# Medusa_9x8.net
KiCad netlist of a schematic drawn in Altium Designer
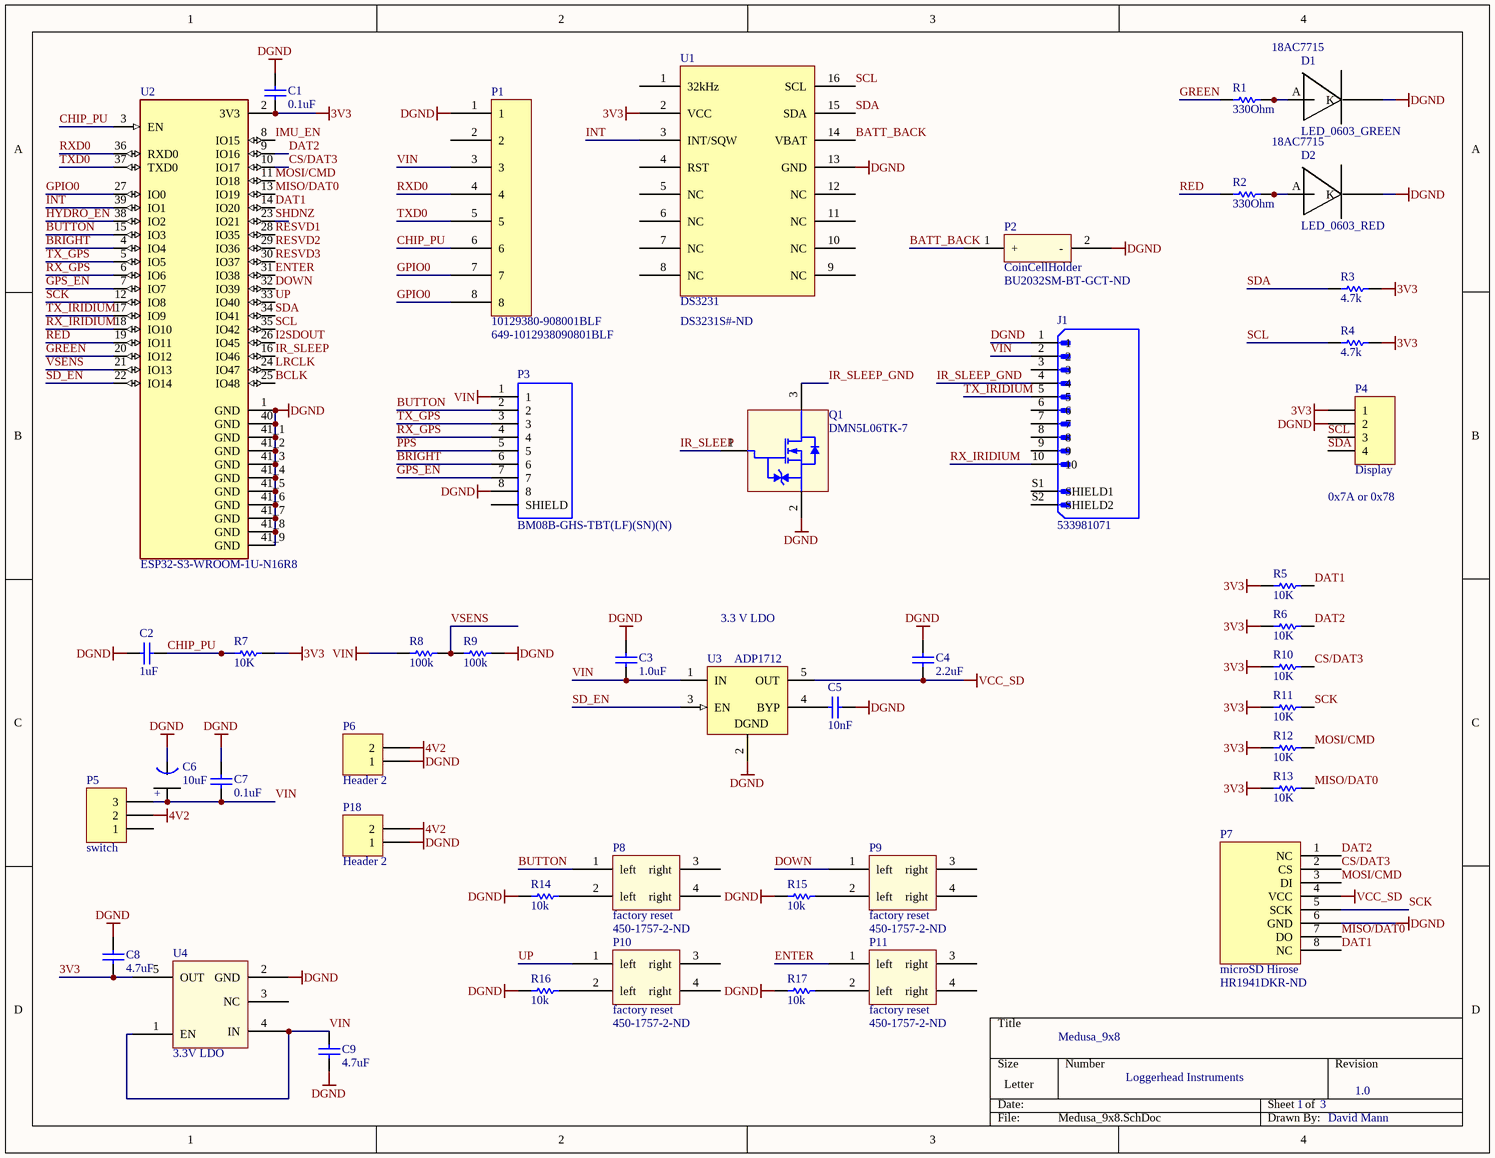
[diagram p0: Medusa_9x8.SchDoc]

(export (version "E")
  (design (tool "Eeschema 10.0.6"))
  (components
    (comp (ref "C1")
      (value "0.1uF")
      (footprint "0402")
      (description "Ceramic Chip Capacitor - Standard")
      (fields (field (name "PUBLISHER") "Altium Limited"))
      (libsource (lib "KEMET Chip Capacitor") (part "C0402"))
    )
    (comp (ref "C2")
      (value "1uF")
      (footprint "0402")
      (description "Ceramic Chip Capacitor - Standard")
      (fields (field (name "PUBLISHER") "Altium Limited"))
      (libsource (lib "KEMET Chip Capacitor") (part "C0402"))
    )
    (comp (ref "C3")
      (value "1.0uF")
      (footprint "0402")
      (description "Ceramic Chip Capacitor - Standard")
      (fields (field (name "PUBLISHER") "Altium Limited"))
      (libsource (lib "KEMET Chip Capacitor") (part "C0402"))
    )
    (comp (ref "C4")
      (value "2.2uF")
      (footprint "0402")
      (description "Ceramic Chip Capacitor - Standard")
      (fields (field (name "PUBLISHER") "Altium Limited"))
      (libsource (lib "KEMET Chip Capacitor") (part "C0402"))
    )
    (comp (ref "C5")
      (value "10nF")
      (footprint "0402")
      (description "Ceramic Chip Capacitor - Standard")
      (fields (field (name "PUBLISHER") "Altium Limited"))
      (libsource (lib "KEMET Chip Capacitor") (part "C0402"))
    )
    (comp (ref "C6") (value "10uF") (footprint "Tant0805") (libsource (lib "Loggerhead") (part "Tant0805")))
    (comp (ref "C7")
      (value "0.1uF")
      (footprint "0402")
      (description "Ceramic Chip Capacitor - Standard")
      (fields (field (name "PUBLISHER") "Altium Limited"))
      (libsource (lib "KEMET Chip Capacitor") (part "C0402"))
    )
    (comp (ref "C8")
      (value "4.7uF")
      (footprint "0402")
      (description "Ceramic Chip Capacitor - Standard")
      (fields (field (name "PUBLISHER") "Altium Limited"))
      (libsource (lib "KEMET Chip Capacitor") (part "C0402"))
    )
    (comp (ref "C9")
      (value "4.7uF")
      (footprint "0402")
      (description "Ceramic Chip Capacitor - Standard")
      (fields (field (name "PUBLISHER") "Altium Limited"))
      (libsource (lib "KEMET Chip Capacitor") (part "C0402"))
    )
    (comp (ref "D1")
      (value "LED_0603_GREEN")
      (footprint "Diode0603")
      (fields (field (name "SUPPLIER PART NUMBER 1") "18AC7715"))
      (libsource (lib "Loggerhead") (part "LED_0603"))
    )
    (comp (ref "D2")
      (value "LED_0603_RED")
      (footprint "Diode0603")
      (fields (field (name "SUPPLIER PART NUMBER 1") "18AC7715"))
      (libsource (lib "Loggerhead") (part "LED_0603"))
    )
    (comp (ref "J1")
      (value "533981071")
      (footprint "MOLEX_533981071")
      (libsource (lib "533981071") (part "533981071"))
    )
    (comp (ref "P1")
      (value "10129380-908001BLF")
      (footprint "Header_8_SMT")
      (description "Surface mount header")
      (fields (field (name "SUPPLIER PART NUMBER 1") "649-1012938090801BLF"))
      (libsource (lib "Loggerhead") (part "Header8_SMT"))
    )
    (comp (ref "P2")
      (value "CoinCellHolder")
      (footprint "CoinCellHolder")
      (fields (field (name "SUPPLIER PART NUMBER 1") "BU2032SM-BT-GCT-ND"))
      (libsource (lib "Loggerhead") (part "CoinCellHolder"))
    )
    (comp (ref "P3")
      (value "BM08B-GHS-TBT(LF)(SN)(N)")
      (footprint "JST_BM08B-GHS-TBT(LF)(SN)(N)")
      (description "Connector Header Surface Mount 8 position 0.049 _1.25mm_")
      (fields (field (name "MF") "JST Sales") (field (name "MP") "BM08B-GHS-TBT_LF__SN__N_"))
      (libsource (lib "BM08B-GHS-TBT_LF__SN__N_") (part "BM08B-GHS-TBT(LF)(SN)(N)"))
    )
    (comp (ref "P4")
      (value "Display")
      (footprint "HDR1X4")
      (description "Header, 4-Pin")
      (fields (field (name "PUBLISHER") "Altium Limited"))
      (libsource (lib "Miscellaneous Connectors") (part "Header 4"))
    )
    (comp (ref "P5")
      (value "switch")
      (footprint "HDR1X3")
      (description "Header, 3-Pin")
      (fields (field (name "PUBLISHER") "Altium Limited"))
      (libsource (lib "Miscellaneous Connectors") (part "Header 3"))
    )
    (comp (ref "P6")
      (value "Header 2")
      (footprint "HDR1X2")
      (description "Header, 2-Pin")
      (fields (field (name "PUBLISHER") "Altium Limited"))
      (libsource (lib "Miscellaneous Connectors") (part "Header 2"))
    )
    (comp (ref "P7")
      (value "microSD Hirose")
      (footprint "DM3D microSD")
      (fields (field (name "SUPPLIER PART NUMBER 1") "HR1941DKR-ND"))
      (libsource (lib "Loggerhead") (part "microSD Hirose"))
    )
    (comp (ref "P8")
      (value "factory reset")
      (footprint "SOP4")
      (fields (field (name "SUPPLIER PART NUMBER 1") "450-1757-2-ND"))
      (libsource (lib "Loggerhead") (part "pushbutton"))
    )
    (comp (ref "P9")
      (value "factory reset")
      (footprint "SOP4")
      (fields (field (name "SUPPLIER PART NUMBER 1") "450-1757-2-ND"))
      (libsource (lib "Loggerhead") (part "pushbutton"))
    )
    (comp (ref "P10")
      (value "factory reset")
      (footprint "SOP4")
      (fields (field (name "SUPPLIER PART NUMBER 1") "450-1757-2-ND"))
      (libsource (lib "Loggerhead") (part "pushbutton"))
    )
    (comp (ref "P11")
      (value "factory reset")
      (footprint "SOP4")
      (fields (field (name "SUPPLIER PART NUMBER 1") "450-1757-2-ND"))
      (libsource (lib "Loggerhead") (part "pushbutton"))
    )
    (comp (ref "P18")
      (value "Header 2")
      (footprint "HDR1X2")
      (description "Header, 2-Pin")
      (fields (field (name "PUBLISHER") "Altium Limited"))
      (libsource (lib "Miscellaneous Connectors") (part "Header 2"))
    )
    (comp (ref "Q1")
      (value "DMN5L06TK-7")
      (footprint "SOT-523")
      (description "Ultra-low leakage Enhanced MOSFET")
      (fields
        (field (name "CREATOR AND DATE") "Will Flanery 2010-09-02")
        (field (name "FOOTPRINT VERIFIED BY") "*")
        (field (name "SCHEMATIC VERIFIED BY") "*")
        (field (name "VENDOR INFO VERIFIED BY") "*")
      )
      (libsource (lib "Flanery") (part "FET DMN5L06TK-7"))
    )
    (comp (ref "R1")
      (value "330Ohm")
      (footprint "2-0402")
      (fields (field (name "PUBLISHER") "Altium Limited"))
      (libsource (lib "Panasonic Resistor") (part "ERJ2RB"))
    )
    (comp (ref "R2")
      (value "330Ohm")
      (footprint "2-0402")
      (fields (field (name "PUBLISHER") "Altium Limited"))
      (libsource (lib "Panasonic Resistor") (part "ERJ2RB"))
    )
    (comp (ref "R3")
      (value "4.7k")
      (footprint "2-0402")
      (fields (field (name "PUBLISHER") "Altium Limited"))
      (libsource (lib "Panasonic Resistor") (part "ERJ2RB"))
    )
    (comp (ref "R4")
      (value "4.7k")
      (footprint "2-0402")
      (fields (field (name "PUBLISHER") "Altium Limited"))
      (libsource (lib "Panasonic Resistor") (part "ERJ2RB"))
    )
    (comp (ref "R5")
      (value "10K")
      (footprint "2-0402")
      (fields (field (name "PUBLISHER") "Altium Limited"))
      (libsource (lib "Panasonic Resistor") (part "ERJ2RB"))
    )
    (comp (ref "R6")
      (value "10K")
      (footprint "2-0402")
      (fields (field (name "PUBLISHER") "Altium Limited"))
      (libsource (lib "Panasonic Resistor") (part "ERJ2RB"))
    )
    (comp (ref "R7")
      (value "10K")
      (footprint "2-0402")
      (fields (field (name "PUBLISHER") "Altium Limited"))
      (libsource (lib "Panasonic Resistor") (part "ERJ2RB"))
    )
    (comp (ref "R8")
      (value "100k")
      (footprint "2-0402")
      (fields (field (name "PUBLISHER") "Altium Limited"))
      (libsource (lib "Panasonic Resistor") (part "ERJ2RB"))
    )
    (comp (ref "R9")
      (value "100k")
      (footprint "2-0402")
      (fields (field (name "PUBLISHER") "Altium Limited"))
      (libsource (lib "Panasonic Resistor") (part "ERJ2RB"))
    )
    (comp (ref "R10")
      (value "10K")
      (footprint "2-0402")
      (fields (field (name "PUBLISHER") "Altium Limited"))
      (libsource (lib "Panasonic Resistor") (part "ERJ2RB"))
    )
    (comp (ref "R11")
      (value "10K")
      (footprint "2-0402")
      (fields (field (name "PUBLISHER") "Altium Limited"))
      (libsource (lib "Panasonic Resistor") (part "ERJ2RB"))
    )
    (comp (ref "R12")
      (value "10K")
      (footprint "2-0402")
      (fields (field (name "PUBLISHER") "Altium Limited"))
      (libsource (lib "Panasonic Resistor") (part "ERJ2RB"))
    )
    (comp (ref "R13")
      (value "10K")
      (footprint "2-0402")
      (fields (field (name "PUBLISHER") "Altium Limited"))
      (libsource (lib "Panasonic Resistor") (part "ERJ2RB"))
    )
    (comp (ref "R14")
      (value "10k")
      (footprint "2-0402")
      (fields (field (name "PUBLISHER") "Altium Limited"))
      (libsource (lib "Panasonic Resistor") (part "ERJ2RB"))
    )
    (comp (ref "R15")
      (value "10k")
      (footprint "2-0402")
      (fields (field (name "PUBLISHER") "Altium Limited"))
      (libsource (lib "Panasonic Resistor") (part "ERJ2RB"))
    )
    (comp (ref "R16")
      (value "10k")
      (footprint "2-0402")
      (fields (field (name "PUBLISHER") "Altium Limited"))
      (libsource (lib "Panasonic Resistor") (part "ERJ2RB"))
    )
    (comp (ref "R17")
      (value "10k")
      (footprint "2-0402")
      (fields (field (name "PUBLISHER") "Altium Limited"))
      (libsource (lib "Panasonic Resistor") (part "ERJ2RB"))
    )
    (comp (ref "U1")
      (value "DS3231")
      (footprint "DS3231")
      (fields (field (name "SUPPLIER PART NUMBER 1") "DS3231S#-ND"))
      (libsource (lib "Loggerhead") (part "DS3231"))
    )
    (comp (ref "U2")
      (value "ESP32-S3-WROOM-1U-N16R8")
      (footprint "XCVR_ESP32-S3-WROOM-1U-N16R8")
      (fields (field (name "MF") "Espressif Systems"))
      (libsource (lib "ESP32-S3-WROOM-1U-N16R8") (part "ESP32-S3-WROOM-1U-N16R8"))
    )
    (comp (ref "U3")
      (value "ADP1712")
      (footprint "MF05A_N")
      (description "Micropower, 150mA Low-Noise Ultra Low-Dropout CMOS Voltage Regulator")
      (fields
        (field (name "PARTNUMBER") "LP3985IM5-3.3")
        (field (name "MANUFACTURER") "National Semiconductor")
        (field (name "PUBLISHER") "Altium Limited")
      )
      (libsource (lib "NSC LDO") (part "LP3985IM5-3.3"))
    )
    (comp (ref "U4")
      (value "3.3V LDO")
      (footprint "AP7361C-33Y5-13")
      (libsource (lib "Loggerhead") (part "AP7361C-33Y5-13"))
    )
  )
  (nets
    (net (code "1") (name "/BATT_BACK") (class "Default")
      (node (ref "P2") (pin "1") (pinfunction "+_1") (pintype "passive"))
      (node (ref "U1") (pin "14") (pinfunction "VBAT_14") (pintype "power_in"))
    )
    (net (code "2") (name "/BCLK") (class "Default")
      (node (ref "U2") (pin "25") (pinfunction "IO48_25") (pintype "bidirectional"))
    )
    (net (code "3") (name "/BRIGHT") (class "Default")
      (node (ref "P3") (pin "6") (pinfunction "6_6") (pintype "passive"))
      (node (ref "U2") (pin "4") (pinfunction "IO4_4") (pintype "bidirectional"))
    )
    (net (code "4") (name "/BUTTON") (class "Default")
      (node (ref "P3") (pin "2") (pinfunction "2_2") (pintype "passive"))
      (node (ref "P8") (pin "1") (pinfunction "left_1") (pintype "passive"))
      (node (ref "U2") (pin "15") (pinfunction "IO3_15") (pintype "bidirectional"))
    )
    (net (code "5") (name "/CHIP_PU") (class "Default")
      (node (ref "C2") (pin "1") (pinfunction "1_1") (pintype "passive"))
      (node (ref "P1") (pin "6") (pinfunction "6_6") (pintype "passive"))
      (node (ref "R7") (pin "2") (pinfunction "2_2") (pintype "passive"))
      (node (ref "U2") (pin "3") (pinfunction "EN_3") (pintype "input"))
    )
    (net (code "6") (name "/CS{slash}DAT3") (class "Default")
      (node (ref "P7") (pin "2") (pinfunction "CS_2") (pintype "passive"))
      (node (ref "R10") (pin "1") (pinfunction "1_1") (pintype "passive"))
      (node (ref "U2") (pin "10") (pinfunction "IO17_10") (pintype "bidirectional"))
    )
    (net (code "7") (name "/DAT1") (class "Default")
      (node (ref "P7") (pin "8") (pinfunction "NC_8") (pintype "passive"))
      (node (ref "R5") (pin "1") (pinfunction "1_1") (pintype "passive"))
      (node (ref "U2") (pin "14") (pinfunction "IO20_14") (pintype "bidirectional"))
    )
    (net (code "8") (name "/DAT2") (class "Default")
      (node (ref "P7") (pin "1") (pinfunction "NC_1") (pintype "passive"))
      (node (ref "R6") (pin "1") (pinfunction "1_1") (pintype "passive"))
      (node (ref "U2") (pin "9") (pinfunction "IO16_9") (pintype "bidirectional"))
    )
    (net (code "9") (name "/DOWN") (class "Default")
      (node (ref "P9") (pin "1") (pinfunction "left_1") (pintype "passive"))
      (node (ref "U2") (pin "32") (pinfunction "IO39_32") (pintype "bidirectional"))
    )
    (net (code "10") (name "/ENTER") (class "Default")
      (node (ref "P11") (pin "1") (pinfunction "left_1") (pintype "passive"))
      (node (ref "U2") (pin "31") (pinfunction "IO38_31") (pintype "bidirectional"))
    )
    (net (code "11") (name "/GPIO0") (class "Default")
      (node (ref "P1") (pin "7") (pinfunction "7_7") (pintype "passive"))
      (node (ref "P1") (pin "8") (pinfunction "8_8") (pintype "passive"))
      (node (ref "U2") (pin "27") (pinfunction "IO0_27") (pintype "bidirectional"))
    )
    (net (code "12") (name "/GPS_EN") (class "Default")
      (node (ref "P3") (pin "7") (pinfunction "7_7") (pintype "passive"))
      (node (ref "U2") (pin "7") (pinfunction "IO7_7") (pintype "bidirectional"))
    )
    (net (code "13") (name "/GREEN") (class "Default")
      (node (ref "R1") (pin "2") (pinfunction "2_2") (pintype "passive"))
      (node (ref "U2") (pin "20") (pinfunction "IO12_20") (pintype "bidirectional"))
    )
    (net (code "14") (name "/HYDRO_EN") (class "Default")
      (node (ref "U2") (pin "38") (pinfunction "IO2_38") (pintype "bidirectional"))
    )
    (net (code "15") (name "/I2SDOUT") (class "Default")
      (node (ref "U2") (pin "26") (pinfunction "IO45_26") (pintype "bidirectional"))
    )
    (net (code "16") (name "/IMU_EN") (class "Default")
      (node (ref "U2") (pin "8") (pinfunction "IO15_8") (pintype "bidirectional"))
    )
    (net (code "17") (name "/INT") (class "Default")
      (node (ref "U1") (pin "3") (pinfunction "INT/SQW_3") (pintype "passive"))
      (node (ref "U2") (pin "39") (pinfunction "IO1_39") (pintype "bidirectional"))
    )
    (net (code "18") (name "/IR_SLEEP") (class "Default")
      (node (ref "Q1") (pin "1") (pinfunction "G_1") (pintype "passive"))
      (node (ref "U2") (pin "16") (pinfunction "IO46_16") (pintype "bidirectional"))
    )
    (net (code "19") (name "/IR_SLEEP_GND") (class "Default")
      (node (ref "J1") (pin "4") (pinfunction "4_4") (pintype "passive"))
      (node (ref "Q1") (pin "3") (pinfunction "D_3") (pintype "passive"))
    )
    (net (code "20") (name "/LRCLK") (class "Default")
      (node (ref "U2") (pin "24") (pinfunction "IO47_24") (pintype "bidirectional"))
    )
    (net (code "21") (name "/MISO{slash}DAT0") (class "Default")
      (node (ref "P7") (pin "7") (pinfunction "DO_7") (pintype "passive"))
      (node (ref "R13") (pin "1") (pinfunction "1_1") (pintype "passive"))
      (node (ref "U2") (pin "13") (pinfunction "IO19_13") (pintype "bidirectional"))
    )
    (net (code "22") (name "/MOSI{slash}CMD") (class "Default")
      (node (ref "P7") (pin "3") (pinfunction "DI_3") (pintype "passive"))
      (node (ref "R12") (pin "1") (pinfunction "1_1") (pintype "passive"))
      (node (ref "U2") (pin "11") (pinfunction "IO18_11") (pintype "bidirectional"))
    )
    (net (code "23") (name "/PPS") (class "Default")
      (node (ref "P3") (pin "5") (pinfunction "5_5") (pintype "passive"))
    )
    (net (code "24") (name "/RED") (class "Default")
      (node (ref "R2") (pin "2") (pinfunction "2_2") (pintype "passive"))
      (node (ref "U2") (pin "19") (pinfunction "IO11_19") (pintype "bidirectional"))
    )
    (net (code "25") (name "/RESVD1") (class "Default")
      (node (ref "U2") (pin "28") (pinfunction "IO35_28") (pintype "bidirectional"))
    )
    (net (code "26") (name "/RESVD2") (class "Default")
      (node (ref "U2") (pin "29") (pinfunction "IO36_29") (pintype "bidirectional"))
    )
    (net (code "27") (name "/RESVD3") (class "Default")
      (node (ref "U2") (pin "30") (pinfunction "IO37_30") (pintype "bidirectional"))
    )
    (net (code "28") (name "/RXD0") (class "Default")
      (node (ref "P1") (pin "4") (pinfunction "4_4") (pintype "passive"))
      (node (ref "U2") (pin "36") (pinfunction "RXD0_36") (pintype "bidirectional"))
    )
    (net (code "29") (name "/RX_GPS") (class "Default")
      (node (ref "P3") (pin "4") (pinfunction "4_4") (pintype "passive"))
      (node (ref "U2") (pin "6") (pinfunction "IO6_6") (pintype "bidirectional"))
    )
    (net (code "30") (name "/RX_IRIDIUM") (class "Default")
      (node (ref "J1") (pin "10") (pinfunction "10_10") (pintype "passive"))
      (node (ref "U2") (pin "18") (pinfunction "IO10_18") (pintype "bidirectional"))
    )
    (net (code "31") (name "/SCK") (class "Default")
      (node (ref "P7") (pin "5") (pinfunction "SCK_5") (pintype "passive"))
      (node (ref "R11") (pin "1") (pinfunction "1_1") (pintype "passive"))
      (node (ref "U2") (pin "12") (pinfunction "IO8_12") (pintype "bidirectional"))
    )
    (net (code "32") (name "/SCL") (class "Default")
      (node (ref "P4") (pin "3") (pinfunction "3_3") (pintype "passive"))
      (node (ref "R4") (pin "2") (pinfunction "2_2") (pintype "passive"))
      (node (ref "U1") (pin "16") (pinfunction "SCL_16") (pintype "passive"))
      (node (ref "U2") (pin "35") (pinfunction "IO42_35") (pintype "bidirectional"))
    )
    (net (code "33") (name "/SDA") (class "Default")
      (node (ref "P4") (pin "4") (pinfunction "4_4") (pintype "passive"))
      (node (ref "R3") (pin "2") (pinfunction "2_2") (pintype "passive"))
      (node (ref "U1") (pin "15") (pinfunction "SDA_15") (pintype "passive"))
      (node (ref "U2") (pin "34") (pinfunction "IO41_34") (pintype "bidirectional"))
    )
    (net (code "34") (name "/SD_EN") (class "Default")
      (node (ref "U2") (pin "22") (pinfunction "IO14_22") (pintype "bidirectional"))
      (node (ref "U3") (pin "3") (pinfunction "EN_3") (pintype "input"))
    )
    (net (code "35") (name "/SHDNZ") (class "Default")
      (node (ref "U2") (pin "23") (pinfunction "IO21_23") (pintype "bidirectional"))
    )
    (net (code "36") (name "/TXD0") (class "Default")
      (node (ref "P1") (pin "5") (pinfunction "5_5") (pintype "passive"))
      (node (ref "U2") (pin "37") (pinfunction "TXD0_37") (pintype "bidirectional"))
    )
    (net (code "37") (name "/TX_GPS") (class "Default")
      (node (ref "P3") (pin "3") (pinfunction "3_3") (pintype "passive"))
      (node (ref "U2") (pin "5") (pinfunction "IO5_5") (pintype "bidirectional"))
    )
    (net (code "38") (name "/TX_IRIDIUM") (class "Default")
      (node (ref "J1") (pin "5") (pinfunction "5_5") (pintype "passive"))
      (node (ref "U2") (pin "17") (pinfunction "IO9_17") (pintype "bidirectional"))
    )
    (net (code "39") (name "/UP") (class "Default")
      (node (ref "P10") (pin "1") (pinfunction "left_1") (pintype "passive"))
      (node (ref "U2") (pin "33") (pinfunction "IO40_33") (pintype "bidirectional"))
    )
    (net (code "40") (name "/VSENS") (class "Default")
      (node (ref "R8") (pin "1") (pinfunction "1_1") (pintype "passive"))
      (node (ref "R9") (pin "2") (pinfunction "2_2") (pintype "passive"))
      (node (ref "U2") (pin "21") (pinfunction "IO13_21") (pintype "bidirectional"))
    )
    (net (code "41") (name "3V3") (class "Default")
      (node (ref "C1") (pin "1") (pinfunction "1_1") (pintype "passive"))
      (node (ref "C8") (pin "2") (pinfunction "2_2") (pintype "passive"))
      (node (ref "P4") (pin "1") (pinfunction "1_1") (pintype "passive"))
      (node (ref "R10") (pin "2") (pinfunction "2_2") (pintype "passive"))
      (node (ref "R11") (pin "2") (pinfunction "2_2") (pintype "passive"))
      (node (ref "R12") (pin "2") (pinfunction "2_2") (pintype "passive"))
      (node (ref "R13") (pin "2") (pinfunction "2_2") (pintype "passive"))
      (node (ref "R3") (pin "1") (pinfunction "1_1") (pintype "passive"))
      (node (ref "R4") (pin "1") (pinfunction "1_1") (pintype "passive"))
      (node (ref "R5") (pin "2") (pinfunction "2_2") (pintype "passive"))
      (node (ref "R6") (pin "2") (pinfunction "2_2") (pintype "passive"))
      (node (ref "R7") (pin "1") (pinfunction "1_1") (pintype "passive"))
      (node (ref "U1") (pin "2") (pinfunction "VCC_2") (pintype "power_in"))
      (node (ref "U2") (pin "2") (pinfunction "3V3_2") (pintype "power_in"))
      (node (ref "U4") (pin "5") (pinfunction "OUT_5") (pintype "passive"))
    )
    (net (code "42") (name "4V2") (class "Default")
      (node (ref "P18") (pin "2") (pinfunction "2_2") (pintype "passive"))
      (node (ref "P5") (pin "2") (pinfunction "2_2") (pintype "passive"))
      (node (ref "P6") (pin "2") (pinfunction "2_2") (pintype "passive"))
    )
    (net (code "43") (name "DGND") (class "Default")
      (node (ref "C1") (pin "2") (pinfunction "2_2") (pintype "passive"))
      (node (ref "C2") (pin "2") (pinfunction "2_2") (pintype "passive"))
      (node (ref "C3") (pin "2") (pinfunction "2_2") (pintype "passive"))
      (node (ref "C4") (pin "2") (pinfunction "2_2") (pintype "passive"))
      (node (ref "C5") (pin "1") (pinfunction "1_1") (pintype "passive"))
      (node (ref "C6") (pin "1") (pinfunction "GND_1") (pintype "passive"))
      (node (ref "C7") (pin "2") (pinfunction "2_2") (pintype "passive"))
      (node (ref "C8") (pin "1") (pinfunction "1_1") (pintype "passive"))
      (node (ref "C9") (pin "2") (pinfunction "2_2") (pintype "passive"))
      (node (ref "D1") (pin "K") (pinfunction "K_K") (pintype "passive"))
      (node (ref "D2") (pin "K") (pinfunction "K_K") (pintype "passive"))
      (node (ref "J1") (pin "1") (pinfunction "1_1") (pintype "passive"))
      (node (ref "P1") (pin "1") (pinfunction "1_1") (pintype "passive"))
      (node (ref "P18") (pin "1") (pinfunction "1_1") (pintype "passive"))
      (node (ref "P2") (pin "2") (pinfunction "-_2") (pintype "passive"))
      (node (ref "P3") (pin "8") (pinfunction "8_8") (pintype "passive"))
      (node (ref "P4") (pin "2") (pinfunction "2_2") (pintype "passive"))
      (node (ref "P6") (pin "1") (pinfunction "1_1") (pintype "passive"))
      (node (ref "P7") (pin "6") (pinfunction "GND_6") (pintype "passive"))
      (node (ref "Q1") (pin "2") (pinfunction "S_2") (pintype "passive"))
      (node (ref "R14") (pin "2") (pinfunction "2_2") (pintype "passive"))
      (node (ref "R15") (pin "2") (pinfunction "2_2") (pintype "passive"))
      (node (ref "R16") (pin "2") (pinfunction "2_2") (pintype "passive"))
      (node (ref "R17") (pin "2") (pinfunction "2_2") (pintype "passive"))
      (node (ref "R9") (pin "1") (pinfunction "1_1") (pintype "passive"))
      (node (ref "U1") (pin "13") (pinfunction "GND_13") (pintype "passive"))
      (node (ref "U2") (pin "1") (pinfunction "GND_1") (pintype "power_in"))
      (node (ref "U2") (pin "40") (pinfunction "GND_40") (pintype "power_in"))
      (node (ref "U2") (pin "41_1") (pinfunction "GND_41_1") (pintype "power_in"))
      (node (ref "U2") (pin "41_2") (pinfunction "GND_41_2") (pintype "power_in"))
      (node (ref "U2") (pin "41_3") (pinfunction "GND_41_3") (pintype "power_in"))
      (node (ref "U2") (pin "41_4") (pinfunction "GND_41_4") (pintype "power_in"))
      (node (ref "U2") (pin "41_5") (pinfunction "GND_41_5") (pintype "power_in"))
      (node (ref "U2") (pin "41_6") (pinfunction "GND_41_6") (pintype "power_in"))
      (node (ref "U2") (pin "41_7") (pinfunction "GND_41_7") (pintype "power_in"))
      (node (ref "U2") (pin "41_8") (pinfunction "GND_41_8") (pintype "power_in"))
      (node (ref "U2") (pin "41_9") (pinfunction "GND_41_9") (pintype "power_in"))
      (node (ref "U3") (pin "2") (pinfunction "GND_2") (pintype "power_in"))
      (node (ref "U4") (pin "2") (pinfunction "GND_2") (pintype "passive"))
    )
    (net (code "44") (name "Net-(D1-PadA)") (class "Default")
      (node (ref "D1") (pin "A") (pinfunction "A_A") (pintype "passive"))
      (node (ref "R1") (pin "1") (pinfunction "1_1") (pintype "passive"))
    )
    (net (code "45") (name "Net-(D2-PadA)") (class "Default")
      (node (ref "D2") (pin "A") (pinfunction "A_A") (pintype "passive"))
      (node (ref "R2") (pin "1") (pinfunction "1_1") (pintype "passive"))
    )
    (net (code "46") (name "Net-(P3-SHIELD-PadP1)") (class "Default")
      (node (ref "P3") (pin "P1") (pinfunction "SHIELD_P1") (pintype "passive"))
      (node (ref "P3") (pin "P2") (pinfunction "SHIELD_P2") (pintype "passive"))
    )
    (net (code "47") (name "Net-(P8-left-Pad2)") (class "Default")
      (node (ref "P8") (pin "2") (pinfunction "left_2") (pintype "passive"))
      (node (ref "R14") (pin "1") (pinfunction "1_1") (pintype "passive"))
    )
    (net (code "48") (name "Net-(P9-left-Pad2)") (class "Default")
      (node (ref "P9") (pin "2") (pinfunction "left_2") (pintype "passive"))
      (node (ref "R15") (pin "1") (pinfunction "1_1") (pintype "passive"))
    )
    (net (code "49") (name "Net-(P10-left-Pad2)") (class "Default")
      (node (ref "P10") (pin "2") (pinfunction "left_2") (pintype "passive"))
      (node (ref "R16") (pin "1") (pinfunction "1_1") (pintype "passive"))
    )
    (net (code "50") (name "Net-(P11-left-Pad2)") (class "Default")
      (node (ref "P11") (pin "2") (pinfunction "left_2") (pintype "passive"))
      (node (ref "R17") (pin "1") (pinfunction "1_1") (pintype "passive"))
    )
    (net (code "51") (name "Net-(U3-BYP)") (class "Default")
      (node (ref "C5") (pin "2") (pinfunction "2_2") (pintype "passive"))
      (node (ref "U3") (pin "4") (pinfunction "BYP_4") (pintype "passive"))
    )
    (net (code "52") (name "VCC_SD") (class "Default")
      (node (ref "C4") (pin "1") (pinfunction "1_1") (pintype "passive"))
      (node (ref "P7") (pin "4") (pinfunction "VCC_4") (pintype "passive"))
      (node (ref "U3") (pin "5") (pinfunction "OUT_5") (pintype "power_in"))
    )
    (net (code "53") (name "VIN") (class "Default")
      (node (ref "C3") (pin "1") (pinfunction "1_1") (pintype "passive"))
      (node (ref "C6") (pin "2") (pinfunction "+_2") (pintype "passive"))
      (node (ref "C7") (pin "1") (pinfunction "1_1") (pintype "passive"))
      (node (ref "C9") (pin "1") (pinfunction "1_1") (pintype "passive"))
      (node (ref "J1") (pin "2") (pinfunction "2_2") (pintype "passive"))
      (node (ref "P1") (pin "3") (pinfunction "3_3") (pintype "passive"))
      (node (ref "P3") (pin "1") (pinfunction "1_1") (pintype "passive"))
      (node (ref "P5") (pin "3") (pinfunction "3_3") (pintype "passive"))
      (node (ref "R8") (pin "2") (pinfunction "2_2") (pintype "passive"))
      (node (ref "U3") (pin "1") (pinfunction "IN_1") (pintype "power_in"))
      (node (ref "U4") (pin "1") (pinfunction "EN_1") (pintype "passive"))
      (node (ref "U4") (pin "4") (pinfunction "IN_4") (pintype "passive"))
    )
    (net (code "54") (name "unconnected-(J1-Pad3)") (class "Default")
      (node (ref "J1") (pin "3") (pinfunction "3_3") (pintype "passive"))
    )
    (net (code "55") (name "unconnected-(J1-Pad6)") (class "Default")
      (node (ref "J1") (pin "6") (pinfunction "6_6") (pintype "passive"))
    )
    (net (code "56") (name "unconnected-(J1-Pad7)") (class "Default")
      (node (ref "J1") (pin "7") (pinfunction "7_7") (pintype "passive"))
    )
    (net (code "57") (name "unconnected-(J1-Pad8)") (class "Default")
      (node (ref "J1") (pin "8") (pinfunction "8_8") (pintype "passive"))
    )
    (net (code "58") (name "unconnected-(J1-Pad9)") (class "Default")
      (node (ref "J1") (pin "9") (pinfunction "9_9") (pintype "passive"))
    )
    (net (code "59") (name "unconnected-(J1-SHIELD1-PadS1)") (class "Default")
      (node (ref "J1") (pin "S1") (pinfunction "SHIELD1_S1") (pintype "passive"))
    )
    (net (code "60") (name "unconnected-(J1-SHIELD2-PadS2)") (class "Default")
      (node (ref "J1") (pin "S2") (pinfunction "SHIELD2_S2") (pintype "passive"))
    )
    (net (code "61") (name "unconnected-(P1-Pad2)") (class "Default")
      (node (ref "P1") (pin "2") (pinfunction "2_2") (pintype "passive"))
    )
    (net (code "62") (name "unconnected-(P5-Pad1)") (class "Default")
      (node (ref "P5") (pin "1") (pinfunction "1_1") (pintype "passive"))
    )
    (net (code "63") (name "unconnected-(P8-right-Pad3)") (class "Default")
      (node (ref "P8") (pin "3") (pinfunction "right_3") (pintype "passive"))
    )
    (net (code "64") (name "unconnected-(P8-right-Pad4)") (class "Default")
      (node (ref "P8") (pin "4") (pinfunction "right_4") (pintype "passive"))
    )
    (net (code "65") (name "unconnected-(P9-right-Pad3)") (class "Default")
      (node (ref "P9") (pin "3") (pinfunction "right_3") (pintype "passive"))
    )
    (net (code "66") (name "unconnected-(P9-right-Pad4)") (class "Default")
      (node (ref "P9") (pin "4") (pinfunction "right_4") (pintype "passive"))
    )
    (net (code "67") (name "unconnected-(P10-right-Pad3)") (class "Default")
      (node (ref "P10") (pin "3") (pinfunction "right_3") (pintype "passive"))
    )
    (net (code "68") (name "unconnected-(P10-right-Pad4)") (class "Default")
      (node (ref "P10") (pin "4") (pinfunction "right_4") (pintype "passive"))
    )
    (net (code "69") (name "unconnected-(P11-right-Pad3)") (class "Default")
      (node (ref "P11") (pin "3") (pinfunction "right_3") (pintype "passive"))
    )
    (net (code "70") (name "unconnected-(P11-right-Pad4)") (class "Default")
      (node (ref "P11") (pin "4") (pinfunction "right_4") (pintype "passive"))
    )
    (net (code "71") (name "unconnected-(U1-32kHz-Pad1)") (class "Default")
      (node (ref "U1") (pin "1") (pinfunction "32kHz_1") (pintype "passive"))
    )
    (net (code "72") (name "unconnected-(U1-NC-Pad5)") (class "Default")
      (node (ref "U1") (pin "5") (pinfunction "NC_5") (pintype "passive"))
    )
    (net (code "73") (name "unconnected-(U1-NC-Pad6)") (class "Default")
      (node (ref "U1") (pin "6") (pinfunction "NC_6") (pintype "passive"))
    )
    (net (code "74") (name "unconnected-(U1-NC-Pad7)") (class "Default")
      (node (ref "U1") (pin "7") (pinfunction "NC_7") (pintype "passive"))
    )
    (net (code "75") (name "unconnected-(U1-NC-Pad8)") (class "Default")
      (node (ref "U1") (pin "8") (pinfunction "NC_8") (pintype "passive"))
    )
    (net (code "76") (name "unconnected-(U1-NC-Pad9)") (class "Default")
      (node (ref "U1") (pin "9") (pinfunction "NC_9") (pintype "passive"))
    )
    (net (code "77") (name "unconnected-(U1-NC-Pad10)") (class "Default")
      (node (ref "U1") (pin "10") (pinfunction "NC_10") (pintype "passive"))
    )
    (net (code "78") (name "unconnected-(U1-NC-Pad11)") (class "Default")
      (node (ref "U1") (pin "11") (pinfunction "NC_11") (pintype "passive"))
    )
    (net (code "79") (name "unconnected-(U1-NC-Pad12)") (class "Default")
      (node (ref "U1") (pin "12") (pinfunction "NC_12") (pintype "passive"))
    )
    (net (code "80") (name "unconnected-(U1-RST-Pad4)") (class "Default")
      (node (ref "U1") (pin "4") (pinfunction "RST_4") (pintype "passive"))
    )
    (net (code "81") (name "unconnected-(U4-NC-Pad3)") (class "Default")
      (node (ref "U4") (pin "3") (pinfunction "NC_3") (pintype "passive"))
    )
  )
)
